# design.net
KiCad netlist of a schematic drawn in Altium Designer
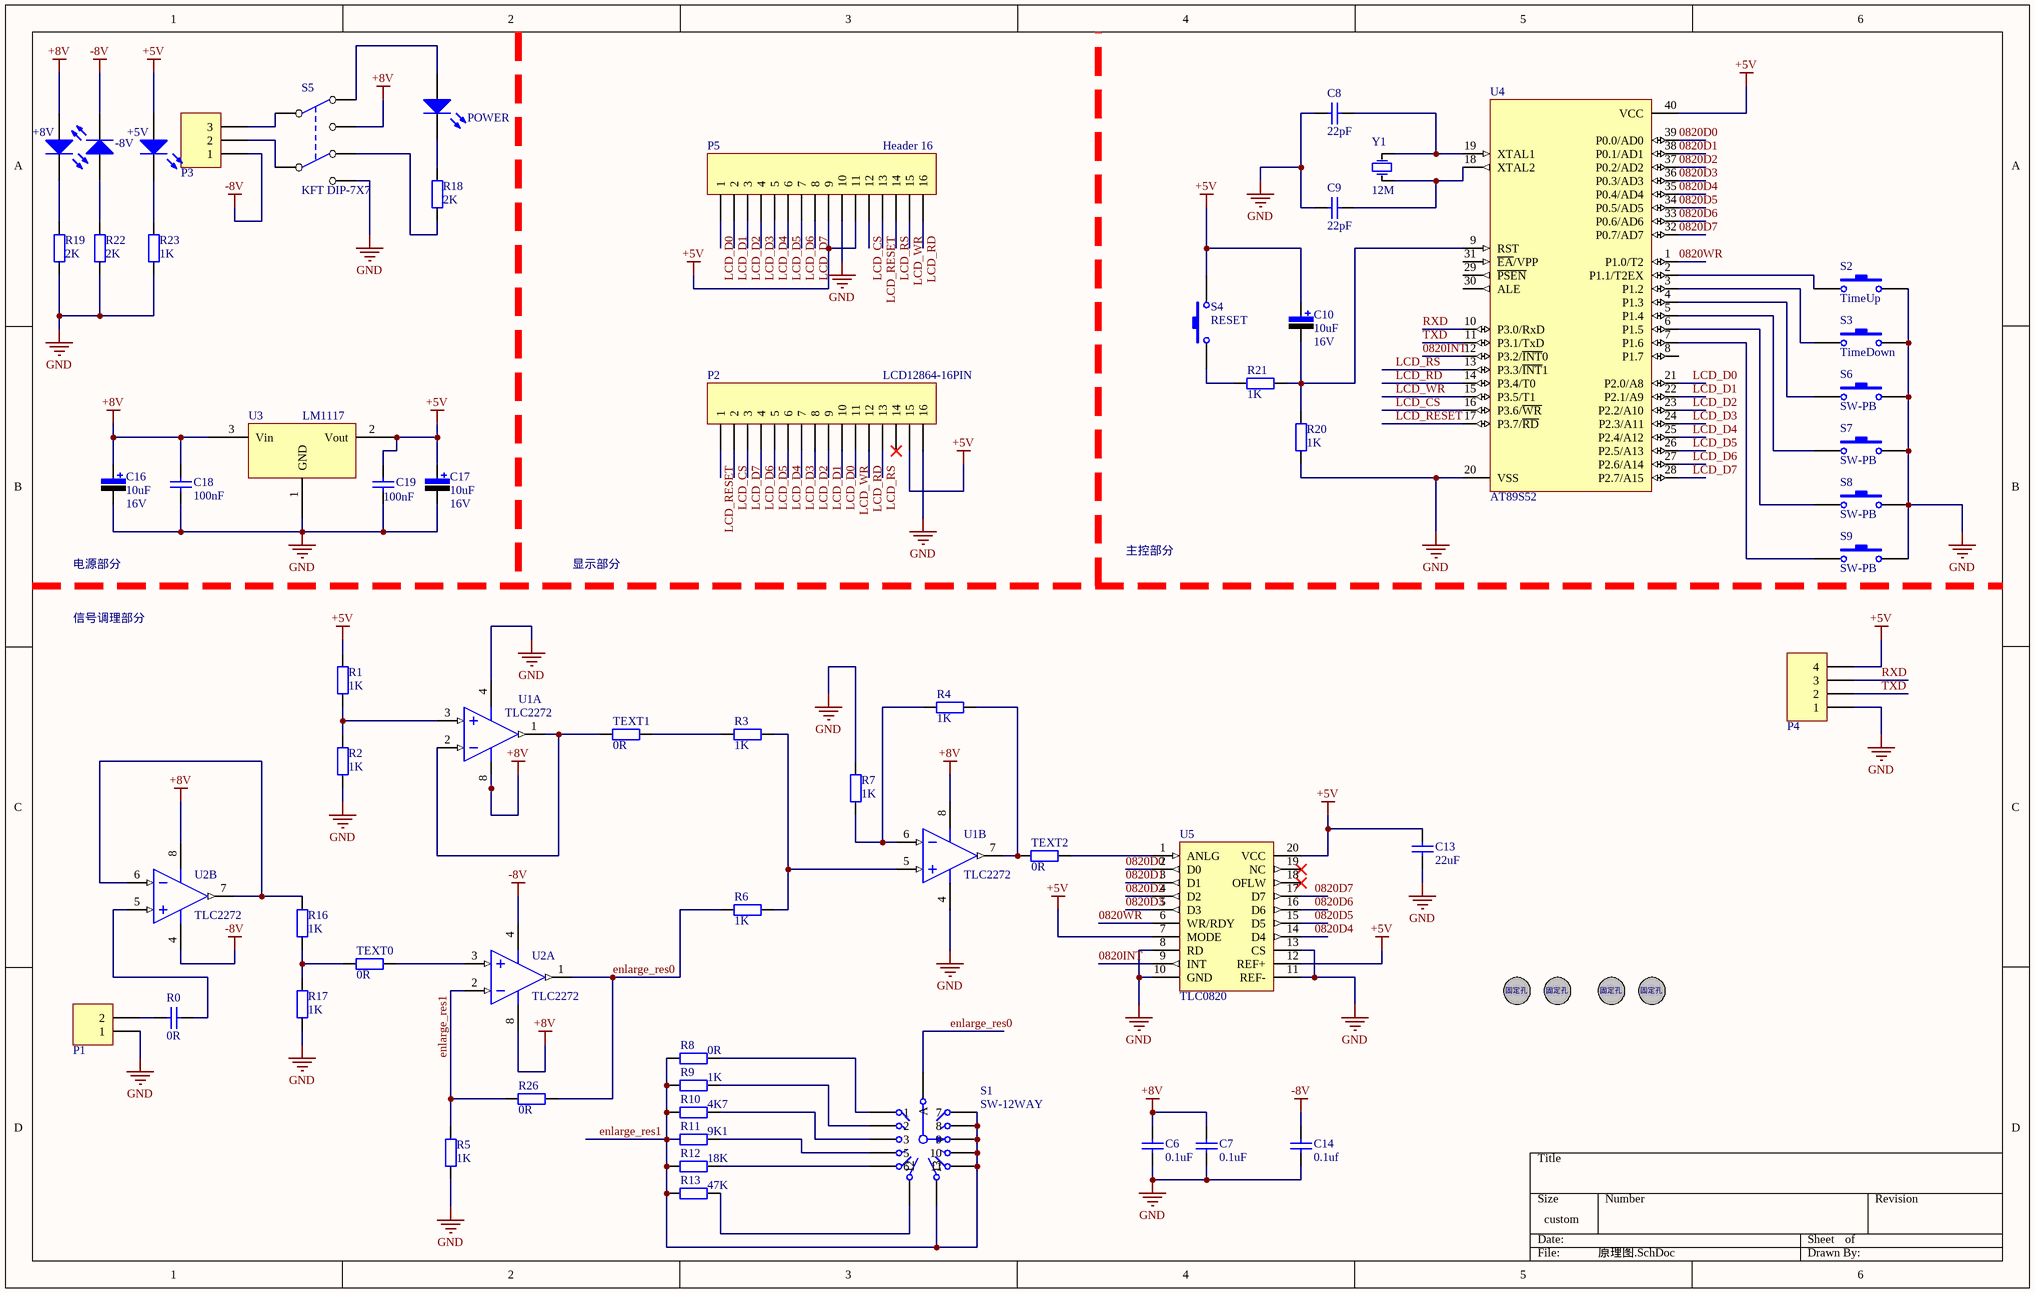
[diagram p0: 原理图.SchDoc]

(export (version "E")
  (design (tool "Eeschema 10.0.6"))
  (components
    (comp (ref "+5V")
      (value "LED0")
      (footprint "LED_0805")
      (description "发光二极管")
      (fields (field (name "PUBLISHER") "Altium Limited"))
      (libsource (lib "Fszhang") (part "LED0"))
    )
    (comp (ref "+8V")
      (value "LED0")
      (footprint "LED_0805")
      (description "发光二极管")
      (fields (field (name "PUBLISHER") "Altium Limited"))
      (libsource (lib "Fszhang") (part "LED0"))
    )
    (comp (ref "-8V")
      (value "LED0")
      (footprint "LED_0805")
      (description "发光二极管")
      (fields (field (name "PUBLISHER") "Altium Limited"))
      (libsource (lib "Fszhang") (part "LED0"))
    )
    (comp (ref "1") (value "3mm固定孔") (footprint "3mm-hole") (libsource (lib "KEA电磁专用") (part "3mm固定孔")))
    (comp (ref "2") (value "3mm固定孔") (footprint "3mm-hole") (libsource (lib "KEA电磁专用") (part "3mm固定孔")))
    (comp (ref "3") (value "3mm固定孔") (footprint "3mm-hole") (libsource (lib "KEA电磁专用") (part "3mm固定孔")))
    (comp (ref "4") (value "3mm固定孔") (footprint "3mm-hole") (libsource (lib "KEA电磁专用") (part "3mm固定孔")))
    (comp (ref "C6")
      (value "0.1uF")
      (footprint "C-RAD-0603")
      (description "无极性电容")
      (fields (field (name "Comment") "Cap") (field (name "PUBLISHER") "Altium Limited"))
      (libsource (lib "Fszhang") (part "Cap"))
    )
    (comp (ref "C7")
      (value "0.1uF")
      (footprint "C-RAD-0603")
      (description "无极性电容")
      (fields (field (name "Comment") "Cap") (field (name "PUBLISHER") "Altium Limited"))
      (libsource (lib "Fszhang") (part "Cap"))
    )
    (comp (ref "C8")
      (value "22pF")
      (footprint "C-RAD-0603")
      (description "无极性电容")
      (fields (field (name "Comment") "Cap") (field (name "PUBLISHER") "Altium Limited"))
      (libsource (lib "Fszhang") (part "Cap"))
    )
    (comp (ref "C9")
      (value "22pF")
      (footprint "C-RAD-0603")
      (description "无极性电容")
      (fields (field (name "Comment") "Cap") (field (name "PUBLISHER") "Altium Limited"))
      (libsource (lib "Fszhang") (part "Cap"))
    )
    (comp (ref "C10")
      (value "10uF")
      (footprint "CAP-3528")
      (description "极性电解电容")
      (fields
        (field (name "VOL") "16V")
        (field (name "Comment") "Cap Pol")
        (field (name "PUBLISHER") "Altium Limited")
      )
      (libsource (lib "Fszhang") (part "Cap Pol"))
    )
    (comp (ref "C13")
      (value "22uF")
      (footprint "C-RAD-0603")
      (description "无极性电容")
      (fields (field (name "Comment") "Cap") (field (name "PUBLISHER") "Altium Limited"))
      (libsource (lib "Fszhang") (part "Cap"))
    )
    (comp (ref "C14")
      (value "0.1uf")
      (footprint "C-RAD-0603")
      (description "无极性电容")
      (fields (field (name "Comment") "Cap") (field (name "PUBLISHER") "Altium Limited"))
      (libsource (lib "Fszhang") (part "Cap"))
    )
    (comp (ref "C16")
      (value "10uF")
      (footprint "CAP-3528")
      (description "极性电解电容")
      (fields
        (field (name "VOL") "16V")
        (field (name "Comment") "Cap Pol")
        (field (name "PUBLISHER") "Altium Limited")
      )
      (libsource (lib "Fszhang") (part "Cap Pol"))
    )
    (comp (ref "C17")
      (value "10uF")
      (footprint "CAP-3528")
      (description "极性电解电容")
      (fields
        (field (name "VOL") "16V")
        (field (name "Comment") "Cap Pol")
        (field (name "PUBLISHER") "Altium Limited")
      )
      (libsource (lib "Fszhang") (part "Cap Pol"))
    )
    (comp (ref "C18")
      (value "100nF")
      (footprint "C-RAD-0603")
      (description "无极性电容")
      (fields (field (name "Comment") "Cap") (field (name "PUBLISHER") "Altium Limited"))
      (libsource (lib "Fszhang") (part "Cap"))
    )
    (comp (ref "C19")
      (value "100nF")
      (footprint "C-RAD-0603")
      (description "无极性电容")
      (fields (field (name "Comment") "Cap") (field (name "PUBLISHER") "Altium Limited"))
      (libsource (lib "Fszhang") (part "Cap"))
    )
    (comp (ref "P1")
      (value "Header 2")
      (footprint "HDR2X1_B2")
      (description "接插件")
      (fields (field (name "PUBLISHER") "Altium Limited"))
      (libsource (lib "Fszhang") (part "Header 2"))
    )
    (comp (ref "P2")
      (value "LCD12864-16PIN")
      (footprint "HDR16X1_A")
      (description "Header16贴片")
      (fields (field (name "PUBLISHER") "Altium Limited"))
      (libsource (lib "Fszhang") (part "Header 16"))
    )
    (comp (ref "P3")
      (value "Header 3")
      (footprint "HDR3X1_B1")
      (description "接插件")
      (fields (field (name "PUBLISHER") "Altium Limited"))
      (libsource (lib "Fszhang") (part "Header 3"))
    )
    (comp (ref "P4")
      (value "Header 4")
      (footprint "HDR4X1_A")
      (description "接插件")
      (fields (field (name "PUBLISHER") "Altium Limited"))
      (libsource (lib "Fszhang") (part "Header 4"))
    )
    (comp (ref "P5")
      (value "Header 16")
      (footprint "HDR16X1_A")
      (description "Header16贴片")
      (fields (field (name "PUBLISHER") "Altium Limited"))
      (libsource (lib "Fszhang") (part "Header 16"))
    )
    (comp (ref "POWER")
      (value "LED0")
      (footprint "LED_0805")
      (description "发光二极管")
      (fields (field (name "PUBLISHER") "Altium Limited"))
      (libsource (lib "Fszhang") (part "LED0"))
    )
    (comp (ref "R0")
      (value "0R")
      (footprint "C-RAD-0603")
      (description "无极性电容")
      (fields (field (name "Comment") "Cap") (field (name "PUBLISHER") "Altium Limited"))
      (libsource (lib "Fszhang") (part "Cap"))
    )
    (comp (ref "R1")
      (value "1K")
      (footprint "0603-1")
      (description "贴片电阻")
      (fields (field (name "Comment") "Res1") (field (name "PUBLISHER") "Altium Limited"))
      (libsource (lib "Fszhang") (part "Res1"))
    )
    (comp (ref "R2")
      (value "1K")
      (footprint "0603-1")
      (description "贴片电阻")
      (fields (field (name "Comment") "Res1") (field (name "PUBLISHER") "Altium Limited"))
      (libsource (lib "Fszhang") (part "Res1"))
    )
    (comp (ref "R3")
      (value "1K")
      (footprint "0603-1")
      (description "贴片电阻")
      (fields (field (name "Comment") "Res1") (field (name "PUBLISHER") "Altium Limited"))
      (libsource (lib "") (part "Res1_1"))
    )
    (comp (ref "R4")
      (value "1K")
      (footprint "0603-1")
      (description "贴片电阻")
      (fields (field (name "Comment") "Res1") (field (name "PUBLISHER") "Altium Limited"))
      (libsource (lib "") (part "Res1_3"))
    )
    (comp (ref "R5")
      (value "1K")
      (footprint "0603-1")
      (description "贴片电阻")
      (fields (field (name "Comment") "Res1") (field (name "PUBLISHER") "Altium Limited"))
      (libsource (lib "Fszhang") (part "Res1"))
    )
    (comp (ref "R6")
      (value "1K")
      (footprint "0603-1")
      (description "贴片电阻")
      (fields (field (name "Comment") "Res1") (field (name "PUBLISHER") "Altium Limited"))
      (libsource (lib "") (part "Res1_1"))
    )
    (comp (ref "R7")
      (value "1K")
      (footprint "0603-1")
      (description "贴片电阻")
      (fields (field (name "Comment") "Res1") (field (name "PUBLISHER") "Altium Limited"))
      (libsource (lib "Fszhang") (part "Res1"))
    )
    (comp (ref "R8")
      (value "0R")
      (footprint "0603-1")
      (description "贴片电阻")
      (fields (field (name "Comment") "Res1") (field (name "PUBLISHER") "Altium Limited"))
      (libsource (lib "") (part "Res1_1"))
    )
    (comp (ref "R9")
      (value "1K")
      (footprint "0603-1")
      (description "贴片电阻")
      (fields (field (name "Comment") "Res1") (field (name "PUBLISHER") "Altium Limited"))
      (libsource (lib "") (part "Res1_1"))
    )
    (comp (ref "R10")
      (value "4K7")
      (footprint "0603-1")
      (description "贴片电阻")
      (fields (field (name "Comment") "Res1") (field (name "PUBLISHER") "Altium Limited"))
      (libsource (lib "") (part "Res1_1"))
    )
    (comp (ref "R11")
      (value "9K1")
      (footprint "0603-1")
      (description "贴片电阻")
      (fields (field (name "Comment") "Res1") (field (name "PUBLISHER") "Altium Limited"))
      (libsource (lib "") (part "Res1_1"))
    )
    (comp (ref "R12")
      (value "18K")
      (footprint "0603-1")
      (description "贴片电阻")
      (fields (field (name "Comment") "Res1") (field (name "PUBLISHER") "Altium Limited"))
      (libsource (lib "") (part "Res1_1"))
    )
    (comp (ref "R13")
      (value "47K")
      (footprint "0603-1")
      (description "贴片电阻")
      (fields (field (name "Comment") "Res1") (field (name "PUBLISHER") "Altium Limited"))
      (libsource (lib "") (part "Res1_1"))
    )
    (comp (ref "R16")
      (value "1K")
      (footprint "0603-1")
      (description "贴片电阻")
      (fields (field (name "Comment") "Res1") (field (name "PUBLISHER") "Altium Limited"))
      (libsource (lib "Fszhang") (part "Res1"))
    )
    (comp (ref "R17")
      (value "1K")
      (footprint "0603-1")
      (description "贴片电阻")
      (fields (field (name "Comment") "Res1") (field (name "PUBLISHER") "Altium Limited"))
      (libsource (lib "") (part "Res1_2"))
    )
    (comp (ref "R18")
      (value "2K")
      (footprint "0603-1")
      (description "贴片电阻")
      (fields (field (name "Comment") "Res1") (field (name "PUBLISHER") "Altium Limited"))
      (libsource (lib "Fszhang") (part "Res1"))
    )
    (comp (ref "R19")
      (value "2K")
      (footprint "0603-1")
      (description "贴片电阻")
      (fields (field (name "Comment") "Res1") (field (name "PUBLISHER") "Altium Limited"))
      (libsource (lib "Fszhang") (part "Res1"))
    )
    (comp (ref "R20")
      (value "1K")
      (footprint "0603-1")
      (description "贴片电阻")
      (fields (field (name "Comment") "Res1") (field (name "PUBLISHER") "Altium Limited"))
      (libsource (lib "Fszhang") (part "Res1"))
    )
    (comp (ref "R21")
      (value "1K")
      (footprint "0603-1")
      (description "贴片电阻")
      (fields (field (name "Comment") "Res1") (field (name "PUBLISHER") "Altium Limited"))
      (libsource (lib "") (part "Res1_1"))
    )
    (comp (ref "R22")
      (value "2K")
      (footprint "0603-1")
      (description "贴片电阻")
      (fields (field (name "Comment") "Res1") (field (name "PUBLISHER") "Altium Limited"))
      (libsource (lib "Fszhang") (part "Res1"))
    )
    (comp (ref "R23")
      (value "1K")
      (footprint "0603-1")
      (description "贴片电阻")
      (fields (field (name "Comment") "Res1") (field (name "PUBLISHER") "Altium Limited"))
      (libsource (lib "Fszhang") (part "Res1"))
    )
    (comp (ref "R26")
      (value "0R")
      (footprint "0603-1")
      (description "贴片电阻")
      (fields (field (name "Comment") "Res1") (field (name "PUBLISHER") "Altium Limited"))
      (libsource (lib "") (part "Res1_1"))
    )
    (comp (ref "S1")
      (value "SW-12WAY")
      (footprint "SW-12WAY")
      (description "12 Way Switch")
      (fields (field (name "PUBLISHER") "Altium Limited"))
      (libsource (lib "Miscellaneous Devices") (part "SW-12WAY"))
    )
    (comp (ref "S2")
      (value "TimeUp")
      (footprint "SMD-6X6X6")
      (description "Switch")
      (fields (field (name "PUBLISHER") "Altium Limited"))
      (libsource (lib "Miscellaneous Devices") (part "SW-PB"))
    )
    (comp (ref "S3")
      (value "TimeDown")
      (footprint "SMD-6X6X6")
      (description "Switch")
      (fields (field (name "PUBLISHER") "Altium Limited"))
      (libsource (lib "Miscellaneous Devices") (part "SW-PB"))
    )
    (comp (ref "S4")
      (value "RESET")
      (footprint "SMD-6X6X6")
      (description "Switch")
      (fields (field (name "PUBLISHER") "Altium Limited"))
      (libsource (lib "Miscellaneous Devices") (part "SW-PB"))
    )
    (comp (ref "S5")
      (value "KFT DIP-7X7")
      (footprint "KFT DIP-7X7")
      (libsource (lib "电源开关") (part "KFT DIP-7X7"))
    )
    (comp (ref "S6")
      (value "SW-PB")
      (footprint "SMD-6X6X6")
      (description "Switch")
      (fields (field (name "PUBLISHER") "Altium Limited"))
      (libsource (lib "Miscellaneous Devices") (part "SW-PB"))
    )
    (comp (ref "S7")
      (value "SW-PB")
      (footprint "SMD-6X6X6")
      (description "Switch")
      (fields (field (name "PUBLISHER") "Altium Limited"))
      (libsource (lib "Miscellaneous Devices") (part "SW-PB"))
    )
    (comp (ref "S8")
      (value "SW-PB")
      (footprint "SMD-6X6X6")
      (description "Switch")
      (fields (field (name "PUBLISHER") "Altium Limited"))
      (libsource (lib "Miscellaneous Devices") (part "SW-PB"))
    )
    (comp (ref "S9")
      (value "SW-PB")
      (footprint "SMD-6X6X6")
      (description "Switch")
      (fields (field (name "PUBLISHER") "Altium Limited"))
      (libsource (lib "Miscellaneous Devices") (part "SW-PB"))
    )
    (comp (ref "TEXT0")
      (value "0R")
      (footprint "0603-1")
      (description "贴片电阻")
      (fields (field (name "Comment") "Res1") (field (name "PUBLISHER") "Altium Limited"))
      (libsource (lib "") (part "Res1_1"))
    )
    (comp (ref "TEXT1")
      (value "0R")
      (footprint "0603-1")
      (description "贴片电阻")
      (fields (field (name "Comment") "Res1") (field (name "PUBLISHER") "Altium Limited"))
      (libsource (lib "") (part "Res1_1"))
    )
    (comp (ref "TEXT2")
      (value "0R")
      (footprint "0603-1")
      (description "贴片电阻")
      (fields (field (name "Comment") "Res1") (field (name "PUBLISHER") "Altium Limited"))
      (libsource (lib "") (part "Res1_1"))
    )
    (comp (ref "U1")
      (value "TLC2272")
      (footprint "SOP8")
      (description "LinCMOS Precision Dual Operational Amplifier")
      (fields (field (name "PUBLISHER") "Altium Limited"))
      (libsource (lib "TI Operational Amplifier") (part "TLC27L2AIDR"))
    )
    (comp (ref "U2")
      (value "TLC2272")
      (footprint "SOP8")
      (description "LinCMOS Precision Dual Operational Amplifier")
      (fields (field (name "PUBLISHER") "Altium Limited"))
      (libsource (lib "TI Operational Amplifier") (part "TLC27L2AIDR"))
    )
    (comp (ref "U3")
      (value "LM1117")
      (footprint "LM1117")
      (description "3端线性稳压器")
      (libsource (lib "KEA电磁专用") (part "LM1117"))
    )
    (comp (ref "U4")
      (value "AT89S52")
      (footprint "DIP-40")
      (description "51系列单片机")
      (fields (field (name "PUBLISHER") "Altium Limited"))
      (libsource (lib "Fszhang") (part "AT89S52"))
    )
    (comp (ref "U5") (value "TLC0820") (footprint "SO20_M") (libsource (lib "TLC0820") (part "TLC0820")))
    (comp (ref "Y1")
      (value "12M")
      (footprint "OSC UM-5")
      (description "晶振")
      (fields (field (name "Comment") "XTAL") (field (name "PUBLISHER") "Altium Limited"))
      (libsource (lib "Fszhang") (part "XTAL"))
    )
  )
  (nets
    (net (code "1") (name "+5V") (class "Default")
      (node (ref "+5V") (pin "1") (pinfunction "A_1") (pintype "passive"))
      (node (ref "C10") (pin "1") (pinfunction "1_1") (pintype "passive"))
      (node (ref "C13") (pin "2") (pinfunction "2_2") (pintype "passive"))
      (node (ref "C17") (pin "1") (pinfunction "1_1") (pintype "passive"))
      (node (ref "C19") (pin "2") (pinfunction "2_2") (pintype "passive"))
      (node (ref "P2") (pin "15") (pinfunction "15_15") (pintype "passive"))
      (node (ref "P4") (pin "4") (pinfunction "4_4") (pintype "passive"))
      (node (ref "P5") (pin "11") (pinfunction "11_11") (pintype "passive"))
      (node (ref "P5") (pin "9") (pinfunction "9_9") (pintype "passive"))
      (node (ref "R1") (pin "2") (pinfunction "2_2") (pintype "passive"))
      (node (ref "S4") (pin "2") (pinfunction "2_2") (pintype "passive"))
      (node (ref "U3") (pin "2") (pinfunction "Vout_2") (pintype "passive"))
      (node (ref "U4") (pin "40") (pinfunction "VCC_40") (pintype "power_in"))
      (node (ref "U5") (pin "12") (pinfunction "REF+_12") (pintype "power_in"))
      (node (ref "U5") (pin "20") (pinfunction "VCC_20") (pintype "power_in"))
      (node (ref "U5") (pin "7") (pinfunction "MODE_7") (pintype "passive"))
    )
    (net (code "2") (name "+8V") (class "Default")
      (node (ref "+8V") (pin "1") (pinfunction "A_1") (pintype "passive"))
      (node (ref "C16") (pin "1") (pinfunction "1_1") (pintype "passive"))
      (node (ref "C18") (pin "2") (pinfunction "2_2") (pintype "passive"))
      (node (ref "C6") (pin "2") (pinfunction "2_2") (pintype "passive"))
      (node (ref "C7") (pin "2") (pinfunction "2_2") (pintype "passive"))
      (node (ref "S5") (pin "1") (pinfunction "1_1") (pintype "passive"))
      (node (ref "U1") (pin "8") (pinfunction "VDD_8") (pintype "power_in"))
      (node (ref "U2") (pin "8") (pinfunction "VDD_8") (pintype "power_in"))
      (node (ref "U3") (pin "3") (pinfunction "Vin_3") (pintype "passive"))
    )
    (net (code "3") (name "-8V") (class "Default")
      (node (ref "-8V") (pin "2") (pinfunction "K_2") (pintype "passive"))
      (node (ref "C14") (pin "2") (pinfunction "2_2") (pintype "passive"))
      (node (ref "P3") (pin "1") (pinfunction "1_1") (pintype "passive"))
      (node (ref "U2") (pin "4") (pinfunction "GND_4") (pintype "power_in"))
    )
    (net (code "4") (name "/0820D0") (class "Default")
      (node (ref "U4") (pin "39") (pinfunction "P0.0/AD0_39") (pintype "bidirectional"))
      (node (ref "U5") (pin "2") (pinfunction "D0_2") (pintype "output"))
    )
    (net (code "5") (name "/0820D1") (class "Default")
      (node (ref "U4") (pin "38") (pinfunction "P0.1/AD1_38") (pintype "bidirectional"))
      (node (ref "U5") (pin "3") (pinfunction "D1_3") (pintype "output"))
    )
    (net (code "6") (name "/0820D2") (class "Default")
      (node (ref "U4") (pin "37") (pinfunction "P0.2/AD2_37") (pintype "bidirectional"))
      (node (ref "U5") (pin "4") (pinfunction "D2_4") (pintype "output"))
    )
    (net (code "7") (name "/0820D3") (class "Default")
      (node (ref "U4") (pin "36") (pinfunction "P0.3/AD3_36") (pintype "bidirectional"))
      (node (ref "U5") (pin "5") (pinfunction "D3_5") (pintype "output"))
    )
    (net (code "8") (name "/0820D4") (class "Default")
      (node (ref "U4") (pin "35") (pinfunction "P0.4/AD4_35") (pintype "bidirectional"))
      (node (ref "U5") (pin "14") (pinfunction "D4_14") (pintype "output"))
    )
    (net (code "9") (name "/0820D5") (class "Default")
      (node (ref "U4") (pin "34") (pinfunction "P0.5/AD5_34") (pintype "bidirectional"))
      (node (ref "U5") (pin "15") (pinfunction "D5_15") (pintype "output"))
    )
    (net (code "10") (name "/0820D6") (class "Default")
      (node (ref "U4") (pin "33") (pinfunction "P0.6/AD6_33") (pintype "bidirectional"))
      (node (ref "U5") (pin "16") (pinfunction "D6_16") (pintype "output"))
    )
    (net (code "11") (name "/0820D7") (class "Default")
      (node (ref "U4") (pin "32") (pinfunction "P0.7/AD7_32") (pintype "bidirectional"))
      (node (ref "U5") (pin "17") (pinfunction "D7_17") (pintype "output"))
    )
    (net (code "12") (name "/0820INT") (class "Default")
      (node (ref "U4") (pin "12") (pinfunction "P3.2/~{INT}0_12") (pintype "bidirectional"))
      (node (ref "U5") (pin "9") (pinfunction "INT_9") (pintype "output"))
    )
    (net (code "13") (name "/0820WR") (class "Default")
      (node (ref "U4") (pin "1") (pinfunction "P1.0/T2_1") (pintype "bidirectional"))
      (node (ref "U5") (pin "6") (pinfunction "WR/RDY_6") (pintype "passive"))
    )
    (net (code "14") (name "/LCD_CS") (class "Default")
      (node (ref "P2") (pin "2") (pinfunction "2_2") (pintype "passive"))
      (node (ref "P5") (pin "12") (pinfunction "12_12") (pintype "passive"))
      (node (ref "U4") (pin "16") (pinfunction "P3.6/~{WR}_16") (pintype "bidirectional"))
    )
    (net (code "15") (name "/LCD_D0") (class "Default")
      (node (ref "P2") (pin "10") (pinfunction "10_10") (pintype "passive"))
      (node (ref "P5") (pin "1") (pinfunction "1_1") (pintype "passive"))
      (node (ref "U4") (pin "21") (pinfunction "P2.0/A8_21") (pintype "bidirectional"))
    )
    (net (code "16") (name "/LCD_D1") (class "Default")
      (node (ref "P2") (pin "9") (pinfunction "9_9") (pintype "passive"))
      (node (ref "P5") (pin "2") (pinfunction "2_2") (pintype "passive"))
      (node (ref "U4") (pin "22") (pinfunction "P2.1/A9_22") (pintype "bidirectional"))
    )
    (net (code "17") (name "/LCD_D2") (class "Default")
      (node (ref "P2") (pin "8") (pinfunction "8_8") (pintype "passive"))
      (node (ref "P5") (pin "3") (pinfunction "3_3") (pintype "passive"))
      (node (ref "U4") (pin "23") (pinfunction "P2.2/A10_23") (pintype "bidirectional"))
    )
    (net (code "18") (name "/LCD_D3") (class "Default")
      (node (ref "P2") (pin "7") (pinfunction "7_7") (pintype "passive"))
      (node (ref "P5") (pin "4") (pinfunction "4_4") (pintype "passive"))
      (node (ref "U4") (pin "24") (pinfunction "P2.3/A11_24") (pintype "bidirectional"))
    )
    (net (code "19") (name "/LCD_D4") (class "Default")
      (node (ref "P2") (pin "6") (pinfunction "6_6") (pintype "passive"))
      (node (ref "P5") (pin "5") (pinfunction "5_5") (pintype "passive"))
      (node (ref "U4") (pin "25") (pinfunction "P2.4/A12_25") (pintype "bidirectional"))
    )
    (net (code "20") (name "/LCD_D5") (class "Default")
      (node (ref "P2") (pin "5") (pinfunction "5_5") (pintype "passive"))
      (node (ref "P5") (pin "6") (pinfunction "6_6") (pintype "passive"))
      (node (ref "U4") (pin "26") (pinfunction "P2.5/A13_26") (pintype "bidirectional"))
    )
    (net (code "21") (name "/LCD_D6") (class "Default")
      (node (ref "P2") (pin "4") (pinfunction "4_4") (pintype "passive"))
      (node (ref "P5") (pin "7") (pinfunction "7_7") (pintype "passive"))
      (node (ref "U4") (pin "27") (pinfunction "P2.6/A14_27") (pintype "bidirectional"))
    )
    (net (code "22") (name "/LCD_D7") (class "Default")
      (node (ref "P2") (pin "3") (pinfunction "3_3") (pintype "passive"))
      (node (ref "P5") (pin "8") (pinfunction "8_8") (pintype "passive"))
      (node (ref "U4") (pin "28") (pinfunction "P2.7/A15_28") (pintype "bidirectional"))
    )
    (net (code "23") (name "/LCD_RD") (class "Default")
      (node (ref "P2") (pin "12") (pinfunction "12_12") (pintype "passive"))
      (node (ref "P5") (pin "16") (pinfunction "16_16") (pintype "passive"))
      (node (ref "U4") (pin "14") (pinfunction "P3.4/T0_14") (pintype "bidirectional"))
    )
    (net (code "24") (name "/LCD_RESET") (class "Default")
      (node (ref "P2") (pin "1") (pinfunction "1_1") (pintype "passive"))
      (node (ref "P5") (pin "13") (pinfunction "13_13") (pintype "passive"))
      (node (ref "U4") (pin "17") (pinfunction "P3.7/~{RD}_17") (pintype "bidirectional"))
    )
    (net (code "25") (name "/LCD_RS") (class "Default")
      (node (ref "P2") (pin "13") (pinfunction "13_13") (pintype "passive"))
      (node (ref "P5") (pin "14") (pinfunction "14_14") (pintype "passive"))
      (node (ref "U4") (pin "13") (pinfunction "P3.3/~{INT}1_13") (pintype "bidirectional"))
    )
    (net (code "26") (name "/LCD_WR") (class "Default")
      (node (ref "P2") (pin "11") (pinfunction "11_11") (pintype "passive"))
      (node (ref "P5") (pin "15") (pinfunction "15_15") (pintype "passive"))
      (node (ref "U4") (pin "15") (pinfunction "P3.5/T1_15") (pintype "bidirectional"))
    )
    (net (code "27") (name "/RXD") (class "Default")
      (node (ref "P4") (pin "3") (pinfunction "3_3") (pintype "passive"))
      (node (ref "U4") (pin "10") (pinfunction "P3.0/RxD_10") (pintype "bidirectional"))
    )
    (net (code "28") (name "/TXD") (class "Default")
      (node (ref "P4") (pin "2") (pinfunction "2_2") (pintype "passive"))
      (node (ref "U4") (pin "11") (pinfunction "P3.1/TxD_11") (pintype "bidirectional"))
    )
    (net (code "29") (name "/enlarge_res0") (class "Default")
      (node (ref "R26") (pin "2") (pinfunction "2_2") (pintype "passive"))
      (node (ref "R6") (pin "1") (pinfunction "1_1") (pintype "passive"))
      (node (ref "S1") (pin "A") (pinfunction "A_A") (pintype "passive"))
      (node (ref "U2") (pin "1") (pinfunction "OUT_1") (pintype "output"))
    )
    (net (code "30") (name "/enlarge_res1") (class "Default")
      (node (ref "R10") (pin "1") (pinfunction "1_1") (pintype "passive"))
      (node (ref "R11") (pin "1") (pinfunction "1_1") (pintype "passive"))
      (node (ref "R12") (pin "1") (pinfunction "1_1") (pintype "passive"))
      (node (ref "R13") (pin "1") (pinfunction "1_1") (pintype "passive"))
      (node (ref "R26") (pin "1") (pinfunction "1_1") (pintype "passive"))
      (node (ref "R5") (pin "2") (pinfunction "2_2") (pintype "passive"))
      (node (ref "R8") (pin "1") (pinfunction "1_1") (pintype "passive"))
      (node (ref "R9") (pin "1") (pinfunction "1_1") (pintype "passive"))
      (node (ref "S1") (pin "10") (pinfunction "10_10") (pintype "passive"))
      (node (ref "S1") (pin "11") (pinfunction "11_11") (pintype "passive"))
      (node (ref "S1") (pin "13") (pinfunction "13_13") (pintype "passive"))
      (node (ref "S1") (pin "7") (pinfunction "7_7") (pintype "passive"))
      (node (ref "S1") (pin "8") (pinfunction "8_8") (pintype "passive"))
      (node (ref "S1") (pin "9") (pinfunction "9_9") (pintype "passive"))
      (node (ref "U2") (pin "2") (pinfunction "IN-_2") (pintype "input"))
    )
    (net (code "31") (name "GND") (class "Default")
      (node (ref "C13") (pin "1") (pinfunction "1_1") (pintype "passive"))
      (node (ref "C14") (pin "1") (pinfunction "1_1") (pintype "passive"))
      (node (ref "C16") (pin "2") (pinfunction "2_2") (pintype "passive"))
      (node (ref "C17") (pin "2") (pinfunction "2_2") (pintype "passive"))
      (node (ref "C18") (pin "1") (pinfunction "1_1") (pintype "passive"))
      (node (ref "C19") (pin "1") (pinfunction "1_1") (pintype "passive"))
      (node (ref "C6") (pin "1") (pinfunction "1_1") (pintype "passive"))
      (node (ref "C7") (pin "1") (pinfunction "1_1") (pintype "passive"))
      (node (ref "C8") (pin "1") (pinfunction "1_1") (pintype "passive"))
      (node (ref "C9") (pin "1") (pinfunction "1_1") (pintype "passive"))
      (node (ref "P1") (pin "1") (pinfunction "1_1") (pintype "passive"))
      (node (ref "P2") (pin "16") (pinfunction "16_16") (pintype "passive"))
      (node (ref "P4") (pin "1") (pinfunction "1_1") (pintype "passive"))
      (node (ref "P5") (pin "10") (pinfunction "10_10") (pintype "passive"))
      (node (ref "R17") (pin "2") (pinfunction "2_2") (pintype "passive"))
      (node (ref "R19") (pin "1") (pinfunction "1_1") (pintype "passive"))
      (node (ref "R2") (pin "1") (pinfunction "1_1") (pintype "passive"))
      (node (ref "R20") (pin "1") (pinfunction "1_1") (pintype "passive"))
      (node (ref "R22") (pin "1") (pinfunction "1_1") (pintype "passive"))
      (node (ref "R23") (pin "1") (pinfunction "1_1") (pintype "passive"))
      (node (ref "R5") (pin "1") (pinfunction "1_1") (pintype "passive"))
      (node (ref "R7") (pin "2") (pinfunction "2_2") (pintype "passive"))
      (node (ref "S2") (pin "2") (pinfunction "2_2") (pintype "passive"))
      (node (ref "S3") (pin "2") (pinfunction "2_2") (pintype "passive"))
      (node (ref "S5") (pin "6") (pinfunction "6_6") (pintype "passive"))
      (node (ref "S6") (pin "2") (pinfunction "2_2") (pintype "passive"))
      (node (ref "S7") (pin "2") (pinfunction "2_2") (pintype "passive"))
      (node (ref "S8") (pin "2") (pinfunction "2_2") (pintype "passive"))
      (node (ref "S9") (pin "2") (pinfunction "2_2") (pintype "passive"))
      (node (ref "U1") (pin "4") (pinfunction "GND_4") (pintype "power_in"))
      (node (ref "U3") (pin "1") (pinfunction "GND_1") (pintype "passive"))
      (node (ref "U4") (pin "20") (pinfunction "VSS_20") (pintype "power_in"))
      (node (ref "U5") (pin "10") (pinfunction "GND_10") (pintype "passive"))
      (node (ref "U5") (pin "11") (pinfunction "REF-_11") (pintype "power_in"))
      (node (ref "U5") (pin "13") (pinfunction "CS_13") (pintype "passive"))
      (node (ref "U5") (pin "8") (pinfunction "RD_8") (pintype "passive"))
    )
    (net (code "32") (name "Net-(+5V-K)") (class "Default")
      (node (ref "+5V") (pin "2") (pinfunction "K_2") (pintype "passive"))
      (node (ref "R23") (pin "2") (pinfunction "2_2") (pintype "passive"))
    )
    (net (code "33") (name "Net-(+8V-K)") (class "Default")
      (node (ref "+8V") (pin "2") (pinfunction "K_2") (pintype "passive"))
      (node (ref "R19") (pin "2") (pinfunction "2_2") (pintype "passive"))
    )
    (net (code "34") (name "Net-(-8V-A)") (class "Default")
      (node (ref "-8V") (pin "1") (pinfunction "A_1") (pintype "passive"))
      (node (ref "R22") (pin "2") (pinfunction "2_2") (pintype "passive"))
    )
    (net (code "35") (name "Net-(P1-Pad2)") (class "Default")
      (node (ref "P1") (pin "2") (pinfunction "2_2") (pintype "passive"))
      (node (ref "R0") (pin "1") (pinfunction "1_1") (pintype "passive"))
    )
    (net (code "36") (name "Net-(P3-Pad2)") (class "Default")
      (node (ref "P3") (pin "2") (pinfunction "2_2") (pintype "passive"))
      (node (ref "S5") (pin "5") (pinfunction "5_5") (pintype "passive"))
    )
    (net (code "37") (name "Net-(P3-Pad3)") (class "Default")
      (node (ref "P3") (pin "3") (pinfunction "3_3") (pintype "passive"))
      (node (ref "S5") (pin "2") (pinfunction "2_2") (pintype "passive"))
    )
    (net (code "38") (name "Net-(POWER-A)") (class "Default")
      (node (ref "POWER") (pin "1") (pinfunction "A_1") (pintype "passive"))
      (node (ref "S5") (pin "3") (pinfunction "3_3") (pintype "passive"))
    )
    (net (code "39") (name "Net-(POWER-K)") (class "Default")
      (node (ref "POWER") (pin "2") (pinfunction "K_2") (pintype "passive"))
      (node (ref "R18") (pin "2") (pinfunction "2_2") (pintype "passive"))
    )
    (net (code "40") (name "Net-(R3-Pad1)") (class "Default")
      (node (ref "R3") (pin "1") (pinfunction "1_1") (pintype "passive"))
      (node (ref "TEXT1") (pin "2") (pinfunction "2_2") (pintype "passive"))
    )
    (net (code "41") (name "Net-(R8-Pad2)") (class "Default")
      (node (ref "R8") (pin "2") (pinfunction "2_2") (pintype "passive"))
      (node (ref "S1") (pin "1") (pinfunction "1_1") (pintype "passive"))
    )
    (net (code "42") (name "Net-(R9-Pad2)") (class "Default")
      (node (ref "R9") (pin "2") (pinfunction "2_2") (pintype "passive"))
      (node (ref "S1") (pin "2") (pinfunction "2_2") (pintype "passive"))
    )
    (net (code "43") (name "Net-(R10-Pad2)") (class "Default")
      (node (ref "R10") (pin "2") (pinfunction "2_2") (pintype "passive"))
      (node (ref "S1") (pin "3") (pinfunction "3_3") (pintype "passive"))
    )
    (net (code "44") (name "Net-(R11-Pad2)") (class "Default")
      (node (ref "R11") (pin "2") (pinfunction "2_2") (pintype "passive"))
      (node (ref "S1") (pin "5") (pinfunction "5_5") (pintype "passive"))
    )
    (net (code "45") (name "Net-(R12-Pad2)") (class "Default")
      (node (ref "R12") (pin "2") (pinfunction "2_2") (pintype "passive"))
      (node (ref "S1") (pin "6") (pinfunction "6_6") (pintype "passive"))
    )
    (net (code "46") (name "Net-(R13-Pad2)") (class "Default")
      (node (ref "R13") (pin "2") (pinfunction "2_2") (pintype "passive"))
      (node (ref "S1") (pin "12") (pinfunction "12_12") (pintype "passive"))
    )
    (net (code "47") (name "Net-(R16-Pad1)") (class "Default")
      (node (ref "R16") (pin "1") (pinfunction "1_1") (pintype "passive"))
      (node (ref "R17") (pin "1") (pinfunction "1_1") (pintype "passive"))
      (node (ref "TEXT0") (pin "1") (pinfunction "1_1") (pintype "passive"))
    )
    (net (code "48") (name "Net-(R18-Pad1)") (class "Default")
      (node (ref "R18") (pin "1") (pinfunction "1_1") (pintype "passive"))
      (node (ref "S5") (pin "4") (pinfunction "4_4") (pintype "passive"))
    )
    (net (code "49") (name "Net-(R21-Pad1)") (class "Default")
      (node (ref "R21") (pin "1") (pinfunction "1_1") (pintype "passive"))
      (node (ref "S4") (pin "1") (pinfunction "1_1") (pintype "passive"))
    )
    (net (code "50") (name "Net-(U1A-IN+)") (class "Default")
      (node (ref "R1") (pin "1") (pinfunction "1_1") (pintype "passive"))
      (node (ref "R2") (pin "2") (pinfunction "2_2") (pintype "passive"))
      (node (ref "U1") (pin "3") (pinfunction "IN+_3") (pintype "input"))
    )
    (net (code "51") (name "Net-(U1A-IN-)") (class "Default")
      (node (ref "TEXT1") (pin "1") (pinfunction "1_1") (pintype "passive"))
      (node (ref "U1") (pin "1") (pinfunction "OUT_1") (pintype "output"))
      (node (ref "U1") (pin "2") (pinfunction "IN-_2") (pintype "input"))
    )
    (net (code "52") (name "Net-(U1B-IN+)") (class "Default")
      (node (ref "R3") (pin "2") (pinfunction "2_2") (pintype "passive"))
      (node (ref "R6") (pin "2") (pinfunction "2_2") (pintype "passive"))
      (node (ref "U1") (pin "5") (pinfunction "IN+_5") (pintype "input"))
    )
    (net (code "53") (name "Net-(U1B-IN-)") (class "Default")
      (node (ref "R4") (pin "2") (pinfunction "2_2") (pintype "passive"))
      (node (ref "R7") (pin "1") (pinfunction "1_1") (pintype "passive"))
      (node (ref "U1") (pin "6") (pinfunction "IN-_6") (pintype "input"))
    )
    (net (code "54") (name "Net-(U1B-OUT)") (class "Default")
      (node (ref "R4") (pin "1") (pinfunction "1_1") (pintype "passive"))
      (node (ref "TEXT2") (pin "1") (pinfunction "1_1") (pintype "passive"))
      (node (ref "U1") (pin "7") (pinfunction "OUT_7") (pintype "output"))
    )
    (net (code "55") (name "Net-(U2A-IN+)") (class "Default")
      (node (ref "TEXT0") (pin "2") (pinfunction "2_2") (pintype "passive"))
      (node (ref "U2") (pin "3") (pinfunction "IN+_3") (pintype "input"))
    )
    (net (code "56") (name "Net-(U2B-IN+)") (class "Default")
      (node (ref "R0") (pin "2") (pinfunction "2_2") (pintype "passive"))
      (node (ref "U2") (pin "5") (pinfunction "IN+_5") (pintype "input"))
    )
    (net (code "57") (name "Net-(U2B-IN-)") (class "Default")
      (node (ref "R16") (pin "2") (pinfunction "2_2") (pintype "passive"))
      (node (ref "U2") (pin "6") (pinfunction "IN-_6") (pintype "input"))
      (node (ref "U2") (pin "7") (pinfunction "OUT_7") (pintype "output"))
    )
    (net (code "58") (name "Net-(U4-P1.1{slash}T2EX)") (class "Default")
      (node (ref "S2") (pin "1") (pinfunction "1_1") (pintype "passive"))
      (node (ref "U4") (pin "2") (pinfunction "P1.1/T2EX_2") (pintype "bidirectional"))
    )
    (net (code "59") (name "Net-(U4-P1.2)") (class "Default")
      (node (ref "S3") (pin "1") (pinfunction "1_1") (pintype "passive"))
      (node (ref "U4") (pin "3") (pinfunction "P1.2_3") (pintype "bidirectional"))
    )
    (net (code "60") (name "Net-(U4-P1.3)") (class "Default")
      (node (ref "S6") (pin "1") (pinfunction "1_1") (pintype "passive"))
      (node (ref "U4") (pin "4") (pinfunction "P1.3_4") (pintype "bidirectional"))
    )
    (net (code "61") (name "Net-(U4-P1.4)") (class "Default")
      (node (ref "S7") (pin "1") (pinfunction "1_1") (pintype "passive"))
      (node (ref "U4") (pin "5") (pinfunction "P1.4_5") (pintype "bidirectional"))
    )
    (net (code "62") (name "Net-(U4-P1.5)") (class "Default")
      (node (ref "S8") (pin "1") (pinfunction "1_1") (pintype "passive"))
      (node (ref "U4") (pin "6") (pinfunction "P1.5_6") (pintype "bidirectional"))
    )
    (net (code "63") (name "Net-(U4-P1.6)") (class "Default")
      (node (ref "S9") (pin "1") (pinfunction "1_1") (pintype "passive"))
      (node (ref "U4") (pin "7") (pinfunction "P1.6_7") (pintype "bidirectional"))
    )
    (net (code "64") (name "Net-(U4-RST)") (class "Default")
      (node (ref "C10") (pin "2") (pinfunction "2_2") (pintype "passive"))
      (node (ref "R20") (pin "2") (pinfunction "2_2") (pintype "passive"))
      (node (ref "R21") (pin "2") (pinfunction "2_2") (pintype "passive"))
      (node (ref "U4") (pin "9") (pinfunction "RST_9") (pintype "input"))
    )
    (net (code "65") (name "Net-(U4-XTAL1)") (class "Default")
      (node (ref "C8") (pin "2") (pinfunction "2_2") (pintype "passive"))
      (node (ref "U4") (pin "19") (pinfunction "XTAL1_19") (pintype "input"))
      (node (ref "Y1") (pin "2") (pinfunction "OSC2_2") (pintype "passive"))
    )
    (net (code "66") (name "Net-(U4-XTAL2)") (class "Default")
      (node (ref "C9") (pin "2") (pinfunction "2_2") (pintype "passive"))
      (node (ref "U4") (pin "18") (pinfunction "XTAL2_18") (pintype "output"))
      (node (ref "Y1") (pin "1") (pinfunction "OSC1_1") (pintype "passive"))
    )
    (net (code "67") (name "Net-(U5-ANLG)") (class "Default")
      (node (ref "TEXT2") (pin "2") (pinfunction "2_2") (pintype "passive"))
      (node (ref "U5") (pin "1") (pinfunction "ANLG_1") (pintype "input"))
    )
    (net (code "68") (name "unconnected-(P2-Pad14)") (class "Default")
      (node (ref "P2") (pin "14") (pinfunction "14_14") (pintype "passive+no_connect"))
    )
    (net (code "69") (name "unconnected-(U4-ALE-Pad30)") (class "Default")
      (node (ref "U4") (pin "30") (pinfunction "ALE_30") (pintype "output"))
    )
    (net (code "70") (name "unconnected-(U4-P1.7-Pad8)") (class "Default")
      (node (ref "U4") (pin "8") (pinfunction "P1.7_8") (pintype "bidirectional"))
    )
    (net (code "71") (name "unconnected-(U4-~{EA}{slash}VPP-Pad31)") (class "Default")
      (node (ref "U4") (pin "31") (pinfunction "~{EA}/VPP_31") (pintype "input"))
    )
    (net (code "72") (name "unconnected-(U4-~{PSEN}-Pad29)") (class "Default")
      (node (ref "U4") (pin "29") (pinfunction "~{PSEN}_29") (pintype "output"))
    )
    (net (code "73") (name "unconnected-(U5-NC-Pad19)") (class "Default")
      (node (ref "U5") (pin "19") (pinfunction "NC_19") (pintype "output+no_connect"))
    )
    (net (code "74") (name "unconnected-(U5-OFLW-Pad18)") (class "Default")
      (node (ref "U5") (pin "18") (pinfunction "OFLW_18") (pintype "output+no_connect"))
    )
  )
)
